# BB_Turret.net
KiCad netlist of a schematic drawn in EAGLE
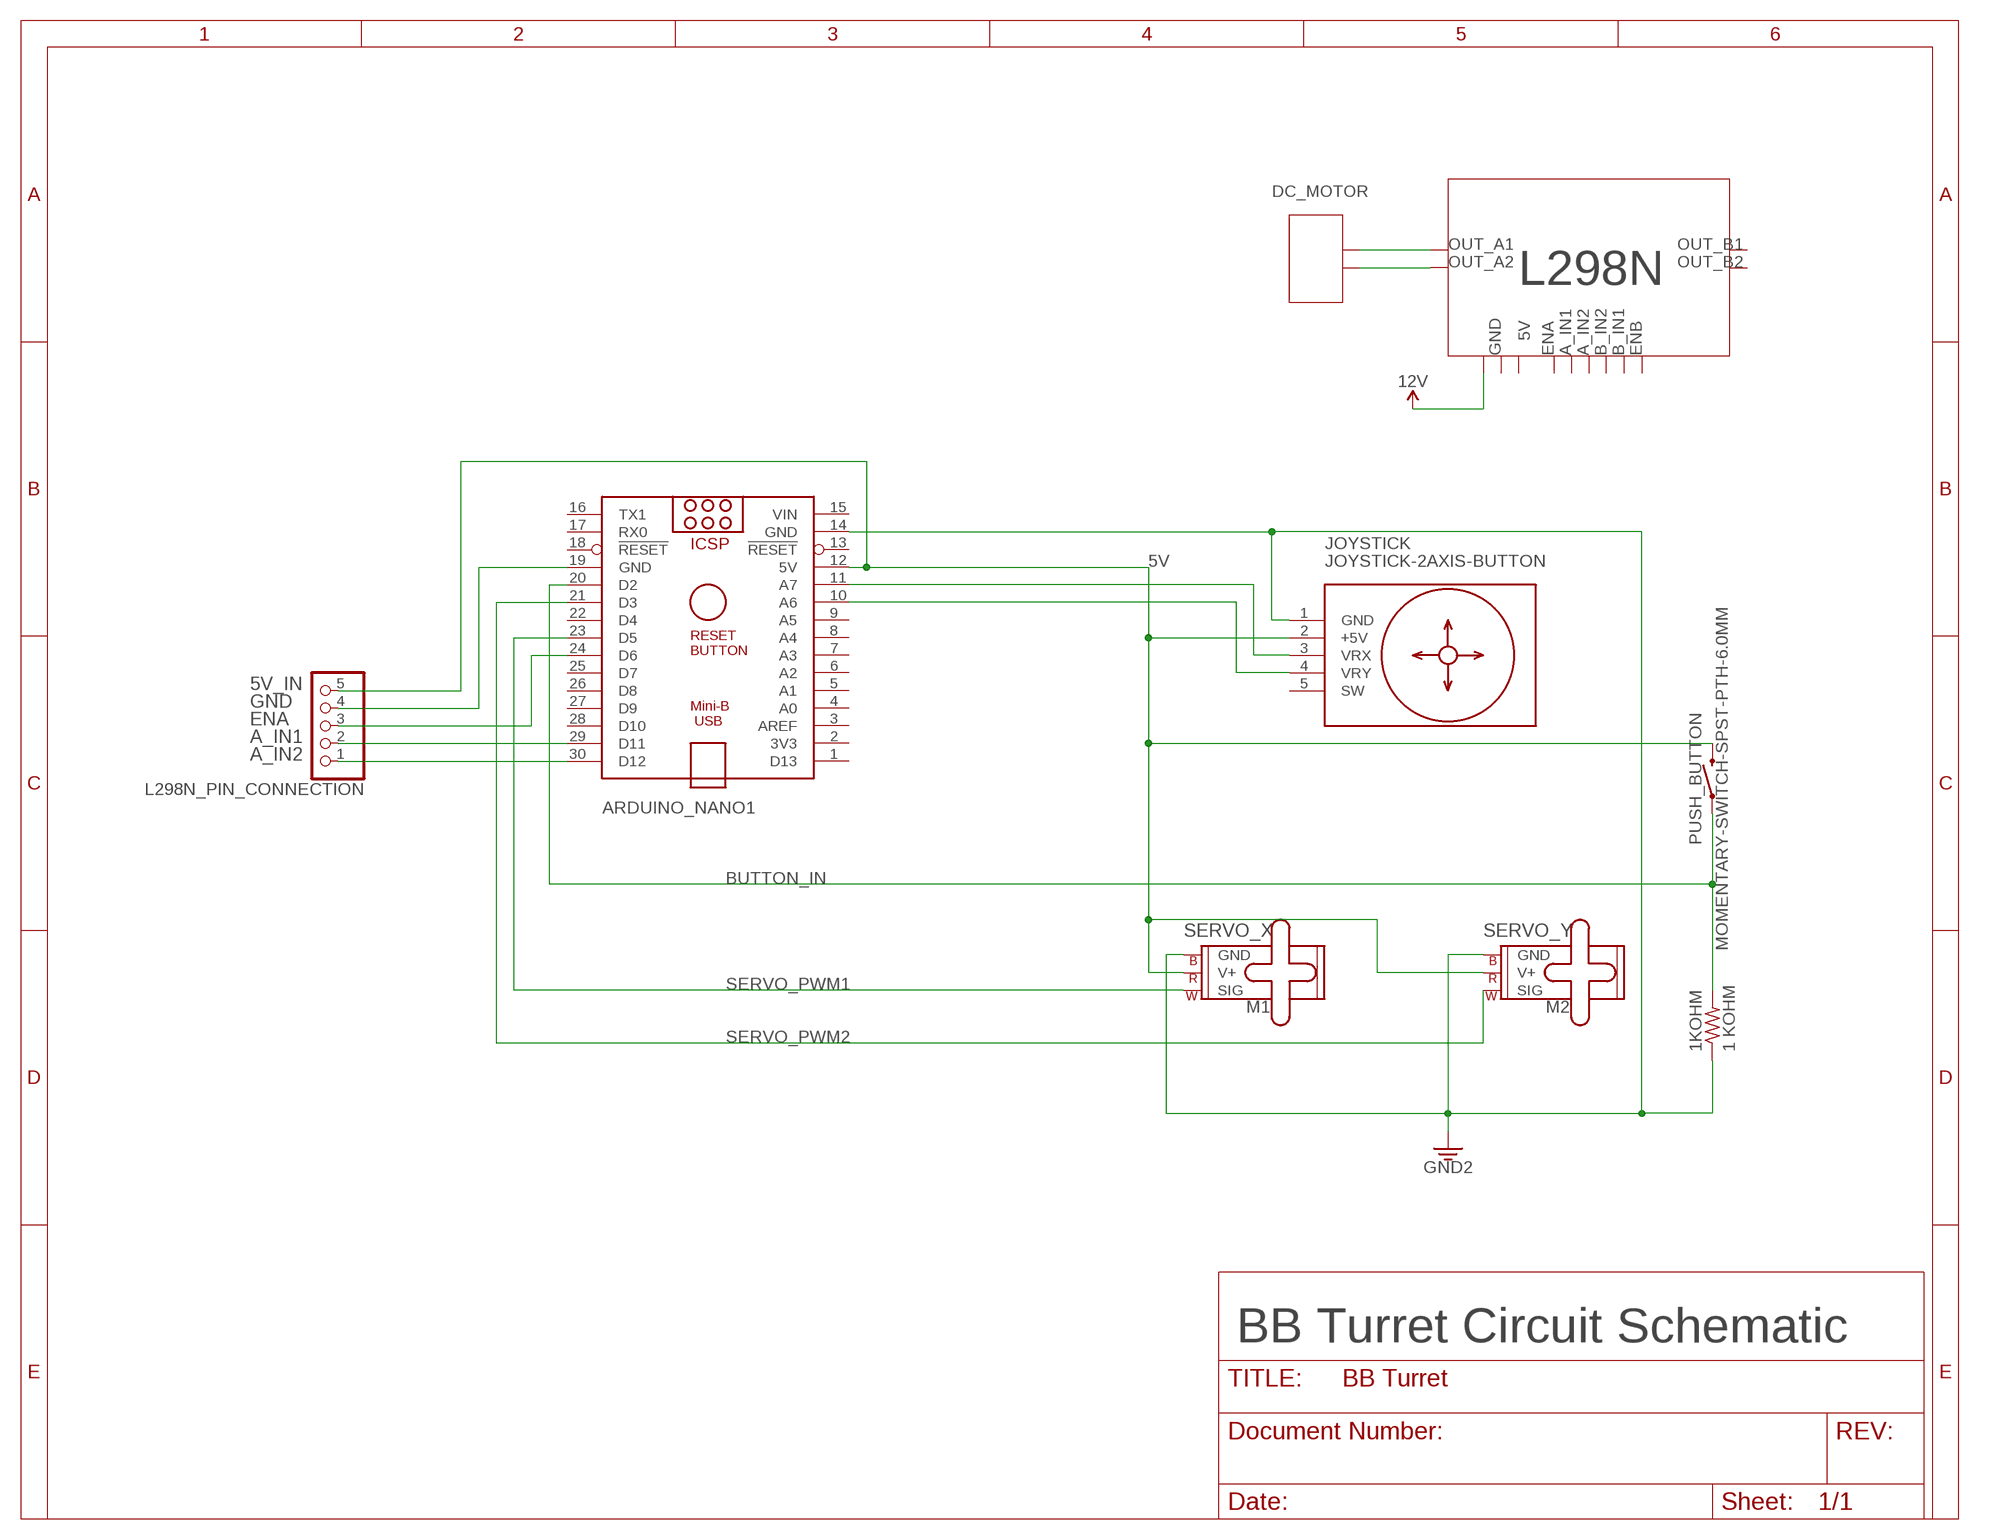
[diagram p0: schematic, sheet 1]

(export (version "E")
  (design (tool "Eeschema 10.0.6"))
  (components
    (comp (ref "1KOHM")
      (value "1 KOHM")
      (footprint "eagle-import:0204_7")
      (libsource (lib "eagle-import") (part "R-US_0204/7"))
    )
    (comp (ref "ARDUINO_NANO1")
      (value "ARDUINO_NANO")
      (footprint "eagle-import:ARDUINO_NANO")
      (libsource (lib "eagle-import") (part "ARDUINO_NANO"))
    )
    (comp (ref "JOYSTICK")
      (value "JOYSTICK-2AXIS-BUTTON")
      (footprint "eagle-import:JOYSTICK-2AXIS-BUTTON")
      (libsource (lib "eagle-import") (part "JOYSTICK-2AXIS-BUTTON"))
    )
    (comp (ref "L298N_PIN_CONNECTION")
      (value "PINHD-1X5")
      (footprint "eagle-import:1X05")
      (libsource (lib "eagle-import") (part "PINHD-1X5"))
    )
    (comp (ref "M1")
      (value "SERVO")
      (footprint "eagle-import:1X03")
      (libsource (lib "eagle-import") (part "SERVO"))
    )
    (comp (ref "M2")
      (value "SERVO")
      (footprint "eagle-import:1X03")
      (libsource (lib "eagle-import") (part "SERVO"))
    )
    (comp (ref "PUSH_BUTTON")
      (value "MOMENTARY-SWITCH-SPST-PTH-6.0MM")
      (footprint "eagle-import:TACTILE_SWITCH_PTH_6.0MM")
      (libsource (lib "eagle-import") (part "MOMENTARY-SWITCH-SPST-PTH-6.0MM"))
    )
  )
  (nets
    (net (code "1") (name "/5V") (class "Default")
      (node (ref "ARDUINO_NANO1") (pin "12") (pinfunction "5V_12") (pintype "power_in"))
      (node (ref "JOYSTICK") (pin "2") (pinfunction "+5V_2") (pintype "power_in"))
      (node (ref "L298N_PIN_CONNECTION") (pin "5") (pinfunction "5_5") (pintype "passive"))
      (node (ref "M1") (pin "2") (pinfunction "V+_2") (pintype "bidirectional"))
      (node (ref "M2") (pin "2") (pinfunction "V+_2") (pintype "bidirectional"))
      (node (ref "PUSH_BUTTON") (pin "3") (pinfunction "2_3") (pintype "passive"))
    )
    (net (code "2") (name "/BUTTON_IN") (class "Default")
      (node (ref "1KOHM") (pin "2") (pinfunction "2_2") (pintype "passive"))
      (node (ref "ARDUINO_NANO1") (pin "20") (pinfunction "D2_20") (pintype "bidirectional"))
      (node (ref "PUSH_BUTTON") (pin "1") (pinfunction "1_1") (pintype "passive"))
    )
    (net (code "3") (name "/SERVO_PWM1") (class "Default")
      (node (ref "ARDUINO_NANO1") (pin "23") (pinfunction "D5_23") (pintype "bidirectional"))
      (node (ref "M1") (pin "1") (pinfunction "SIG_1") (pintype "bidirectional"))
    )
    (net (code "4") (name "/SERVO_PWM2") (class "Default")
      (node (ref "ARDUINO_NANO1") (pin "21") (pinfunction "D3_21") (pintype "bidirectional"))
      (node (ref "M2") (pin "1") (pinfunction "SIG_1") (pintype "bidirectional"))
    )
    (net (code "5") (name "/VIN") (class "Default")
      (node (ref "ARDUINO_NANO1") (pin "15") (pinfunction "VIN_15") (pintype "power_in"))
    )
    (net (code "7") (name "GND2") (class "Default")
      (node (ref "1KOHM") (pin "1") (pinfunction "1_1") (pintype "passive"))
      (node (ref "ARDUINO_NANO1") (pin "14") (pinfunction "GND_14") (pintype "power_in"))
      (node (ref "ARDUINO_NANO1") (pin "19") (pinfunction "GND_19") (pintype "power_in"))
      (node (ref "JOYSTICK") (pin "1") (pinfunction "GND_1") (pintype "power_in"))
      (node (ref "L298N_PIN_CONNECTION") (pin "4") (pinfunction "4_4") (pintype "passive"))
      (node (ref "M1") (pin "3") (pinfunction "GND_3") (pintype "bidirectional"))
      (node (ref "M2") (pin "3") (pinfunction "GND_3") (pintype "bidirectional"))
    )
    (net (code "8") (name "Net-(ARDUINO_NANO1-A6)") (class "Default")
      (node (ref "ARDUINO_NANO1") (pin "10") (pinfunction "A6_10") (pintype "bidirectional"))
      (node (ref "JOYSTICK") (pin "4") (pinfunction "VRY_4") (pintype "passive"))
    )
    (net (code "9") (name "Net-(ARDUINO_NANO1-A7)") (class "Default")
      (node (ref "ARDUINO_NANO1") (pin "11") (pinfunction "A7_11") (pintype "bidirectional"))
      (node (ref "JOYSTICK") (pin "3") (pinfunction "VRX_3") (pintype "passive"))
    )
    (net (code "10") (name "Net-(ARDUINO_NANO1-D6)") (class "Default")
      (node (ref "ARDUINO_NANO1") (pin "24") (pinfunction "D6_24") (pintype "bidirectional"))
      (node (ref "L298N_PIN_CONNECTION") (pin "3") (pinfunction "3_3") (pintype "passive"))
    )
    (net (code "11") (name "Net-(ARDUINO_NANO1-D11)") (class "Default")
      (node (ref "ARDUINO_NANO1") (pin "29") (pinfunction "D11_29") (pintype "bidirectional"))
      (node (ref "L298N_PIN_CONNECTION") (pin "2") (pinfunction "2_2") (pintype "passive"))
    )
    (net (code "12") (name "Net-(ARDUINO_NANO1-D12)") (class "Default")
      (node (ref "ARDUINO_NANO1") (pin "30") (pinfunction "D12_30") (pintype "bidirectional"))
      (node (ref "L298N_PIN_CONNECTION") (pin "1") (pinfunction "1_1") (pintype "passive"))
    )
    (net (code "13") (name "unconnected-(ARDUINO_NANO1-3V3-Pad2)") (class "Default")
      (node (ref "ARDUINO_NANO1") (pin "2") (pinfunction "3V3_2") (pintype "output"))
    )
    (net (code "14") (name "unconnected-(ARDUINO_NANO1-A0-Pad4)") (class "Default")
      (node (ref "ARDUINO_NANO1") (pin "4") (pinfunction "A0_4") (pintype "bidirectional"))
    )
    (net (code "15") (name "unconnected-(ARDUINO_NANO1-A1-Pad5)") (class "Default")
      (node (ref "ARDUINO_NANO1") (pin "5") (pinfunction "A1_5") (pintype "bidirectional"))
    )
    (net (code "16") (name "unconnected-(ARDUINO_NANO1-A2-Pad6)") (class "Default")
      (node (ref "ARDUINO_NANO1") (pin "6") (pinfunction "A2_6") (pintype "bidirectional"))
    )
    (net (code "17") (name "unconnected-(ARDUINO_NANO1-A3-Pad7)") (class "Default")
      (node (ref "ARDUINO_NANO1") (pin "7") (pinfunction "A3_7") (pintype "bidirectional"))
    )
    (net (code "18") (name "unconnected-(ARDUINO_NANO1-A4-Pad8)") (class "Default")
      (node (ref "ARDUINO_NANO1") (pin "8") (pinfunction "A4_8") (pintype "bidirectional"))
    )
    (net (code "19") (name "unconnected-(ARDUINO_NANO1-A5-Pad9)") (class "Default")
      (node (ref "ARDUINO_NANO1") (pin "9") (pinfunction "A5_9") (pintype "bidirectional"))
    )
    (net (code "20") (name "unconnected-(ARDUINO_NANO1-AREF-Pad3)") (class "Default")
      (node (ref "ARDUINO_NANO1") (pin "3") (pinfunction "AREF_3") (pintype "input"))
    )
    (net (code "21") (name "unconnected-(ARDUINO_NANO1-D4-Pad22)") (class "Default")
      (node (ref "ARDUINO_NANO1") (pin "22") (pinfunction "D4_22") (pintype "bidirectional"))
    )
    (net (code "22") (name "unconnected-(ARDUINO_NANO1-D7-Pad25)") (class "Default")
      (node (ref "ARDUINO_NANO1") (pin "25") (pinfunction "D7_25") (pintype "bidirectional"))
    )
    (net (code "23") (name "unconnected-(ARDUINO_NANO1-D8-Pad26)") (class "Default")
      (node (ref "ARDUINO_NANO1") (pin "26") (pinfunction "D8_26") (pintype "bidirectional"))
    )
    (net (code "24") (name "unconnected-(ARDUINO_NANO1-D9-Pad27)") (class "Default")
      (node (ref "ARDUINO_NANO1") (pin "27") (pinfunction "D9_27") (pintype "bidirectional"))
    )
    (net (code "25") (name "unconnected-(ARDUINO_NANO1-D10-Pad28)") (class "Default")
      (node (ref "ARDUINO_NANO1") (pin "28") (pinfunction "D10_28") (pintype "bidirectional"))
    )
    (net (code "26") (name "unconnected-(ARDUINO_NANO1-D13-Pad1)") (class "Default")
      (node (ref "ARDUINO_NANO1") (pin "1") (pinfunction "D13_1") (pintype "bidirectional"))
    )
    (net (code "27") (name "unconnected-(ARDUINO_NANO1-RX0-Pad17)") (class "Default")
      (node (ref "ARDUINO_NANO1") (pin "17") (pinfunction "RX0_17") (pintype "bidirectional"))
    )
    (net (code "28") (name "unconnected-(ARDUINO_NANO1-TX1-Pad16)") (class "Default")
      (node (ref "ARDUINO_NANO1") (pin "16") (pinfunction "TX1_16") (pintype "bidirectional"))
    )
    (net (code "29") (name "unconnected-(ARDUINO_NANO1-~{RESET}-Pad13)") (class "Default")
      (node (ref "ARDUINO_NANO1") (pin "13") (pinfunction "~{RESET}_13") (pintype "input"))
    )
    (net (code "30") (name "unconnected-(ARDUINO_NANO1-~{RESET}-Pad18)") (class "Default")
      (node (ref "ARDUINO_NANO1") (pin "18") (pinfunction "~{RESET}_18") (pintype "input"))
    )
    (net (code "31") (name "unconnected-(JOYSTICK-SW-Pad5)") (class "Default")
      (node (ref "JOYSTICK") (pin "5") (pinfunction "SW_5") (pintype "passive"))
    )
  )
)
